# dIn.net
KiCad netlist of a schematic drawn in Altium Designer
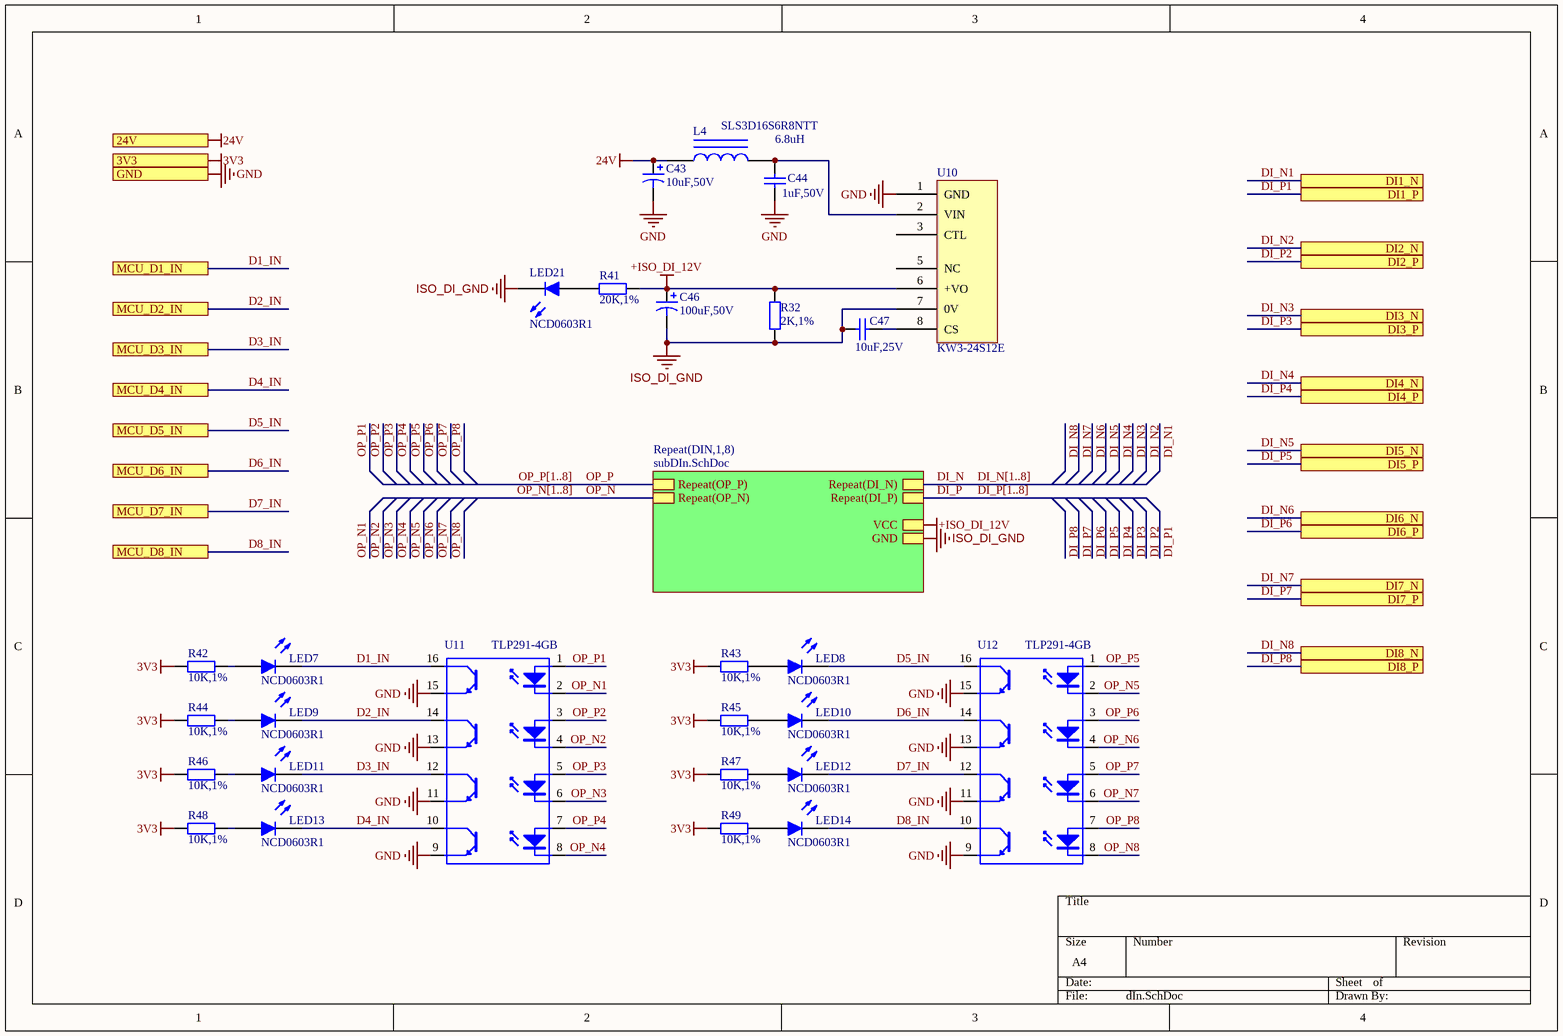
[diagram p0: dIn.SchDoc]

(export (version "E")
  (design (tool "Eeschema 10.0.6"))
  (components
    (comp (ref "C43")
      (value "10uF,50V")
      (footprint "CAP-TH_BD5.0-P2.00-D0.8-FD")
      (description "有极电容")
      (libsource (lib "散件") (part "有极电容"))
    )
    (comp (ref "C44")
      (value "1uF,50V")
      (footprint "C0603")
      (description "无极电容")
      (libsource (lib "电阻电容") (part "无极电容"))
    )
    (comp (ref "C46")
      (value "100uF,50V")
      (footprint "CAP-TH_BD6.3-P2.50-D1.0-FD")
      (description "有极电容")
      (libsource (lib "散件") (part "有极电容"))
    )
    (comp (ref "C47")
      (value "10uF,25V")
      (footprint "C0805")
      (description "无极电容")
      (libsource (lib "电阻电容") (part "无极电容"))
    )
    (comp (ref "L4")
      (value "SLS3D16S6R8NTT")
      (footprint "IND-SMD_L4.0-W4.0_SLS3DXX")
      (description "Magnetic-Core Inductor")
      (fields (field (name "ALTIUM_VALUE") "6.8uH") (field (name "PUBLISHER") "Altium Limited"))
      (libsource (lib "Miscellaneous Devices") (part "Inductor Iron"))
    )
    (comp (ref "LED7")
      (value "NCD0603R1")
      (footprint "LED0603-RD")
      (description "Typical INFRARED GaAs LED")
      (libsource (lib "Schlib1") (part "LED0603"))
    )
    (comp (ref "LED8")
      (value "NCD0603R1")
      (footprint "LED0603-RD")
      (description "Typical INFRARED GaAs LED")
      (libsource (lib "Schlib1") (part "LED0603"))
    )
    (comp (ref "LED9")
      (value "NCD0603R1")
      (footprint "LED0603-RD")
      (description "Typical INFRARED GaAs LED")
      (libsource (lib "Schlib1") (part "LED0603"))
    )
    (comp (ref "LED10")
      (value "NCD0603R1")
      (footprint "LED0603-RD")
      (description "Typical INFRARED GaAs LED")
      (libsource (lib "Schlib1") (part "LED0603"))
    )
    (comp (ref "LED11")
      (value "NCD0603R1")
      (footprint "LED0603-RD")
      (description "Typical INFRARED GaAs LED")
      (libsource (lib "Schlib1") (part "LED0603"))
    )
    (comp (ref "LED12")
      (value "NCD0603R1")
      (footprint "LED0603-RD")
      (description "Typical INFRARED GaAs LED")
      (libsource (lib "Schlib1") (part "LED0603"))
    )
    (comp (ref "LED13")
      (value "NCD0603R1")
      (footprint "LED0603-RD")
      (description "Typical INFRARED GaAs LED")
      (libsource (lib "Schlib1") (part "LED0603"))
    )
    (comp (ref "LED14")
      (value "NCD0603R1")
      (footprint "LED0603-RD")
      (description "Typical INFRARED GaAs LED")
      (libsource (lib "Schlib1") (part "LED0603"))
    )
    (comp (ref "LED21")
      (value "NCD0603R1")
      (footprint "LED0603-RD")
      (description "Typical INFRARED GaAs LED")
      (libsource (lib "Schlib1") (part "LED0603"))
    )
    (comp (ref "R32")
      (value "2K,1%")
      (footprint "R0603")
      (description "电阻")
      (libsource (lib "") (part "电阻_2"))
    )
    (comp (ref "R41")
      (value "20K,1%")
      (footprint "R0603")
      (description "电阻")
      (libsource (lib "") (part "电阻_3"))
    )
    (comp (ref "R42")
      (value "10K,1%")
      (footprint "R0603")
      (description "电阻")
      (libsource (lib "") (part "电阻_1"))
    )
    (comp (ref "R43")
      (value "10K,1%")
      (footprint "R0603")
      (description "电阻")
      (libsource (lib "") (part "电阻_1"))
    )
    (comp (ref "R44")
      (value "10K,1%")
      (footprint "R0603")
      (description "电阻")
      (libsource (lib "") (part "电阻_1"))
    )
    (comp (ref "R45")
      (value "10K,1%")
      (footprint "R0603")
      (description "电阻")
      (libsource (lib "") (part "电阻_1"))
    )
    (comp (ref "R46")
      (value "10K,1%")
      (footprint "R0603")
      (description "电阻")
      (libsource (lib "电阻电容") (part "电阻"))
    )
    (comp (ref "R47")
      (value "10K,1%")
      (footprint "R0603")
      (description "电阻")
      (libsource (lib "电阻电容") (part "电阻"))
    )
    (comp (ref "R48")
      (value "10K,1%")
      (footprint "R0603")
      (description "电阻")
      (libsource (lib "电阻电容") (part "电阻"))
    )
    (comp (ref "R49")
      (value "10K,1%")
      (footprint "R0603")
      (description "电阻")
      (libsource (lib "电阻电容") (part "电阻"))
    )
    (comp (ref "U10")
      (value "KW3-24S12E")
      (footprint "PWRM-TH_WRA2415S-3WR2")
      (description "3W，宽电压输入，隔离稳压输出 DC/DC 模块电源")
      (libsource (lib "Schlib1") (part "KW3-24S12E"))
    )
    (comp (ref "U11")
      (value "TLP291-4GB")
      (footprint "SOP-16_L10.3-W4.4-P1.27-LS7.0-BL")
      (libsource (lib "*") (part "TLP624-4"))
    )
    (comp (ref "U12")
      (value "TLP291-4GB")
      (footprint "SOP-16_L10.3-W4.4-P1.27-LS7.0-BL")
      (libsource (lib "*") (part "TLP624-4"))
    )
  )
  (nets
    (net (code "1") (name "+ISO_DI_12V") (class "Default")
      (node (ref "C46") (pin "1") (pinfunction "1_1") (pintype "passive"))
      (node (ref "R32") (pin "2") (pinfunction "2_2") (pintype "passive"))
      (node (ref "R41") (pin "2") (pinfunction "2_2") (pintype "passive"))
      (node (ref "U10") (pin "6") (pinfunction "+VO_6") (pintype "passive"))
    )
    (net (code "2") (name "/D1_IN") (class "Default")
      (node (ref "LED7") (pin "1") (pinfunction "K_1") (pintype "passive"))
      (node (ref "U11") (pin "16") (pinfunction "C_16") (pintype "passive"))
    )
    (net (code "3") (name "/D2_IN") (class "Default")
      (node (ref "LED9") (pin "1") (pinfunction "K_1") (pintype "passive"))
      (node (ref "U11") (pin "14") (pinfunction "C_14") (pintype "passive"))
    )
    (net (code "4") (name "/D3_IN") (class "Default")
      (node (ref "LED11") (pin "1") (pinfunction "K_1") (pintype "passive"))
      (node (ref "U11") (pin "12") (pinfunction "C_12") (pintype "passive"))
    )
    (net (code "5") (name "/D4_IN") (class "Default")
      (node (ref "LED13") (pin "1") (pinfunction "K_1") (pintype "passive"))
      (node (ref "U11") (pin "10") (pinfunction "C_10") (pintype "passive"))
    )
    (net (code "6") (name "/D5_IN") (class "Default")
      (node (ref "LED8") (pin "1") (pinfunction "K_1") (pintype "passive"))
      (node (ref "U12") (pin "16") (pinfunction "C_16") (pintype "passive"))
    )
    (net (code "7") (name "/D6_IN") (class "Default")
      (node (ref "LED10") (pin "1") (pinfunction "K_1") (pintype "passive"))
      (node (ref "U12") (pin "14") (pinfunction "C_14") (pintype "passive"))
    )
    (net (code "8") (name "/D7_IN") (class "Default")
      (node (ref "LED12") (pin "1") (pinfunction "K_1") (pintype "passive"))
      (node (ref "U12") (pin "12") (pinfunction "C_12") (pintype "passive"))
    )
    (net (code "9") (name "/D8_IN") (class "Default")
      (node (ref "LED14") (pin "1") (pinfunction "K_1") (pintype "passive"))
      (node (ref "U12") (pin "10") (pinfunction "C_10") (pintype "passive"))
    )
    (net (code "31") (name "/OP_N1") (class "Default")
      (node (ref "U11") (pin "2") (pinfunction "K_2") (pintype "passive"))
    )
    (net (code "32") (name "/OP_N2") (class "Default")
      (node (ref "U11") (pin "4") (pinfunction "K_4") (pintype "passive"))
    )
    (net (code "33") (name "/OP_N3") (class "Default")
      (node (ref "U11") (pin "6") (pinfunction "K_6") (pintype "passive"))
    )
    (net (code "34") (name "/OP_N4") (class "Default")
      (node (ref "U11") (pin "8") (pinfunction "K_8") (pintype "passive"))
    )
    (net (code "35") (name "/OP_N5") (class "Default")
      (node (ref "U12") (pin "2") (pinfunction "K_2") (pintype "passive"))
    )
    (net (code "36") (name "/OP_N6") (class "Default")
      (node (ref "U12") (pin "4") (pinfunction "K_4") (pintype "passive"))
    )
    (net (code "37") (name "/OP_N7") (class "Default")
      (node (ref "U12") (pin "6") (pinfunction "K_6") (pintype "passive"))
    )
    (net (code "38") (name "/OP_N8") (class "Default")
      (node (ref "U12") (pin "8") (pinfunction "K_8") (pintype "passive"))
    )
    (net (code "41") (name "/OP_P1") (class "Default")
      (node (ref "U11") (pin "1") (pinfunction "1_1") (pintype "passive"))
    )
    (net (code "42") (name "/OP_P2") (class "Default")
      (node (ref "U11") (pin "3") (pinfunction "A_3") (pintype "passive"))
    )
    (net (code "43") (name "/OP_P3") (class "Default")
      (node (ref "U11") (pin "5") (pinfunction "A_5") (pintype "passive"))
    )
    (net (code "44") (name "/OP_P4") (class "Default")
      (node (ref "U11") (pin "7") (pinfunction "A_7") (pintype "passive"))
    )
    (net (code "45") (name "/OP_P5") (class "Default")
      (node (ref "U12") (pin "1") (pinfunction "1_1") (pintype "passive"))
    )
    (net (code "46") (name "/OP_P6") (class "Default")
      (node (ref "U12") (pin "3") (pinfunction "A_3") (pintype "passive"))
    )
    (net (code "47") (name "/OP_P7") (class "Default")
      (node (ref "U12") (pin "5") (pinfunction "A_5") (pintype "passive"))
    )
    (net (code "48") (name "/OP_P8") (class "Default")
      (node (ref "U12") (pin "7") (pinfunction "A_7") (pintype "passive"))
    )
    (net (code "50") (name "3V3") (class "Default")
      (node (ref "R42") (pin "2") (pinfunction "2_2") (pintype "passive"))
      (node (ref "R43") (pin "2") (pinfunction "2_2") (pintype "passive"))
      (node (ref "R44") (pin "2") (pinfunction "2_2") (pintype "passive"))
      (node (ref "R45") (pin "2") (pinfunction "2_2") (pintype "passive"))
      (node (ref "R46") (pin "2") (pinfunction "2_2") (pintype "passive"))
      (node (ref "R47") (pin "2") (pinfunction "2_2") (pintype "passive"))
      (node (ref "R48") (pin "2") (pinfunction "2_2") (pintype "passive"))
      (node (ref "R49") (pin "2") (pinfunction "2_2") (pintype "passive"))
    )
    (net (code "51") (name "24V") (class "Default")
      (node (ref "C43") (pin "1") (pinfunction "1_1") (pintype "passive"))
      (node (ref "L4") (pin "1") (pinfunction "1_1") (pintype "passive"))
    )
    (net (code "52") (name "GND") (class "Default")
      (node (ref "C43") (pin "2") (pinfunction "2_2") (pintype "passive"))
      (node (ref "C44") (pin "1") (pinfunction "1_1") (pintype "passive"))
      (node (ref "U10") (pin "1") (pinfunction "GND_1") (pintype "passive"))
      (node (ref "U11") (pin "11") (pinfunction "E_11") (pintype "passive"))
      (node (ref "U11") (pin "13") (pinfunction "E_13") (pintype "passive"))
      (node (ref "U11") (pin "15") (pinfunction "E_15") (pintype "passive"))
      (node (ref "U11") (pin "9") (pinfunction "E_9") (pintype "passive"))
      (node (ref "U12") (pin "11") (pinfunction "E_11") (pintype "passive"))
      (node (ref "U12") (pin "13") (pinfunction "E_13") (pintype "passive"))
      (node (ref "U12") (pin "15") (pinfunction "E_15") (pintype "passive"))
      (node (ref "U12") (pin "9") (pinfunction "E_9") (pintype "passive"))
    )
    (net (code "53") (name "ISO_DI_GND") (class "Default")
      (node (ref "C46") (pin "2") (pinfunction "2_2") (pintype "passive"))
      (node (ref "C47") (pin "1") (pinfunction "1_1") (pintype "passive"))
      (node (ref "LED21") (pin "1") (pinfunction "K_1") (pintype "passive"))
      (node (ref "R32") (pin "1") (pinfunction "1_1") (pintype "passive"))
      (node (ref "U10") (pin "7") (pinfunction "0V_7") (pintype "passive"))
    )
    (net (code "54") (name "Net-(LED7-A)") (class "Default")
      (node (ref "LED7") (pin "2") (pinfunction "A_2") (pintype "passive"))
      (node (ref "R42") (pin "1") (pinfunction "1_1") (pintype "passive"))
    )
    (net (code "55") (name "Net-(LED8-A)") (class "Default")
      (node (ref "LED8") (pin "2") (pinfunction "A_2") (pintype "passive"))
      (node (ref "R43") (pin "1") (pinfunction "1_1") (pintype "passive"))
    )
    (net (code "56") (name "Net-(LED9-A)") (class "Default")
      (node (ref "LED9") (pin "2") (pinfunction "A_2") (pintype "passive"))
      (node (ref "R44") (pin "1") (pinfunction "1_1") (pintype "passive"))
    )
    (net (code "57") (name "Net-(LED10-A)") (class "Default")
      (node (ref "LED10") (pin "2") (pinfunction "A_2") (pintype "passive"))
      (node (ref "R45") (pin "1") (pinfunction "1_1") (pintype "passive"))
    )
    (net (code "58") (name "Net-(LED11-A)") (class "Default")
      (node (ref "LED11") (pin "2") (pinfunction "A_2") (pintype "passive"))
      (node (ref "R46") (pin "1") (pinfunction "1_1") (pintype "passive"))
    )
    (net (code "59") (name "Net-(LED12-A)") (class "Default")
      (node (ref "LED12") (pin "2") (pinfunction "A_2") (pintype "passive"))
      (node (ref "R47") (pin "1") (pinfunction "1_1") (pintype "passive"))
    )
    (net (code "60") (name "Net-(LED13-A)") (class "Default")
      (node (ref "LED13") (pin "2") (pinfunction "A_2") (pintype "passive"))
      (node (ref "R48") (pin "1") (pinfunction "1_1") (pintype "passive"))
    )
    (net (code "61") (name "Net-(LED14-A)") (class "Default")
      (node (ref "LED14") (pin "2") (pinfunction "A_2") (pintype "passive"))
      (node (ref "R49") (pin "1") (pinfunction "1_1") (pintype "passive"))
    )
    (net (code "62") (name "Net-(LED21-A)") (class "Default")
      (node (ref "LED21") (pin "2") (pinfunction "A_2") (pintype "passive"))
      (node (ref "R41") (pin "1") (pinfunction "1_1") (pintype "passive"))
    )
    (net (code "63") (name "Net-(U10-CS)") (class "Default")
      (node (ref "C47") (pin "2") (pinfunction "2_2") (pintype "passive"))
      (node (ref "U10") (pin "8") (pinfunction "CS_8") (pintype "passive"))
    )
    (net (code "64") (name "Net-(U10-VIN)") (class "Default")
      (node (ref "C44") (pin "2") (pinfunction "2_2") (pintype "passive"))
      (node (ref "L4") (pin "2") (pinfunction "2_2") (pintype "passive"))
      (node (ref "U10") (pin "2") (pinfunction "VIN_2") (pintype "passive"))
    )
    (net (code "65") (name "unconnected-(U10-CTL-Pad3)") (class "Default")
      (node (ref "U10") (pin "3") (pinfunction "CTL_3") (pintype "passive"))
    )
    (net (code "66") (name "unconnected-(U10-NC-Pad5)") (class "Default")
      (node (ref "U10") (pin "5") (pinfunction "NC_5") (pintype "passive"))
    )
  )
)
